# ir-24v.net
KiCad netlist of a schematic drawn in Altium Designer
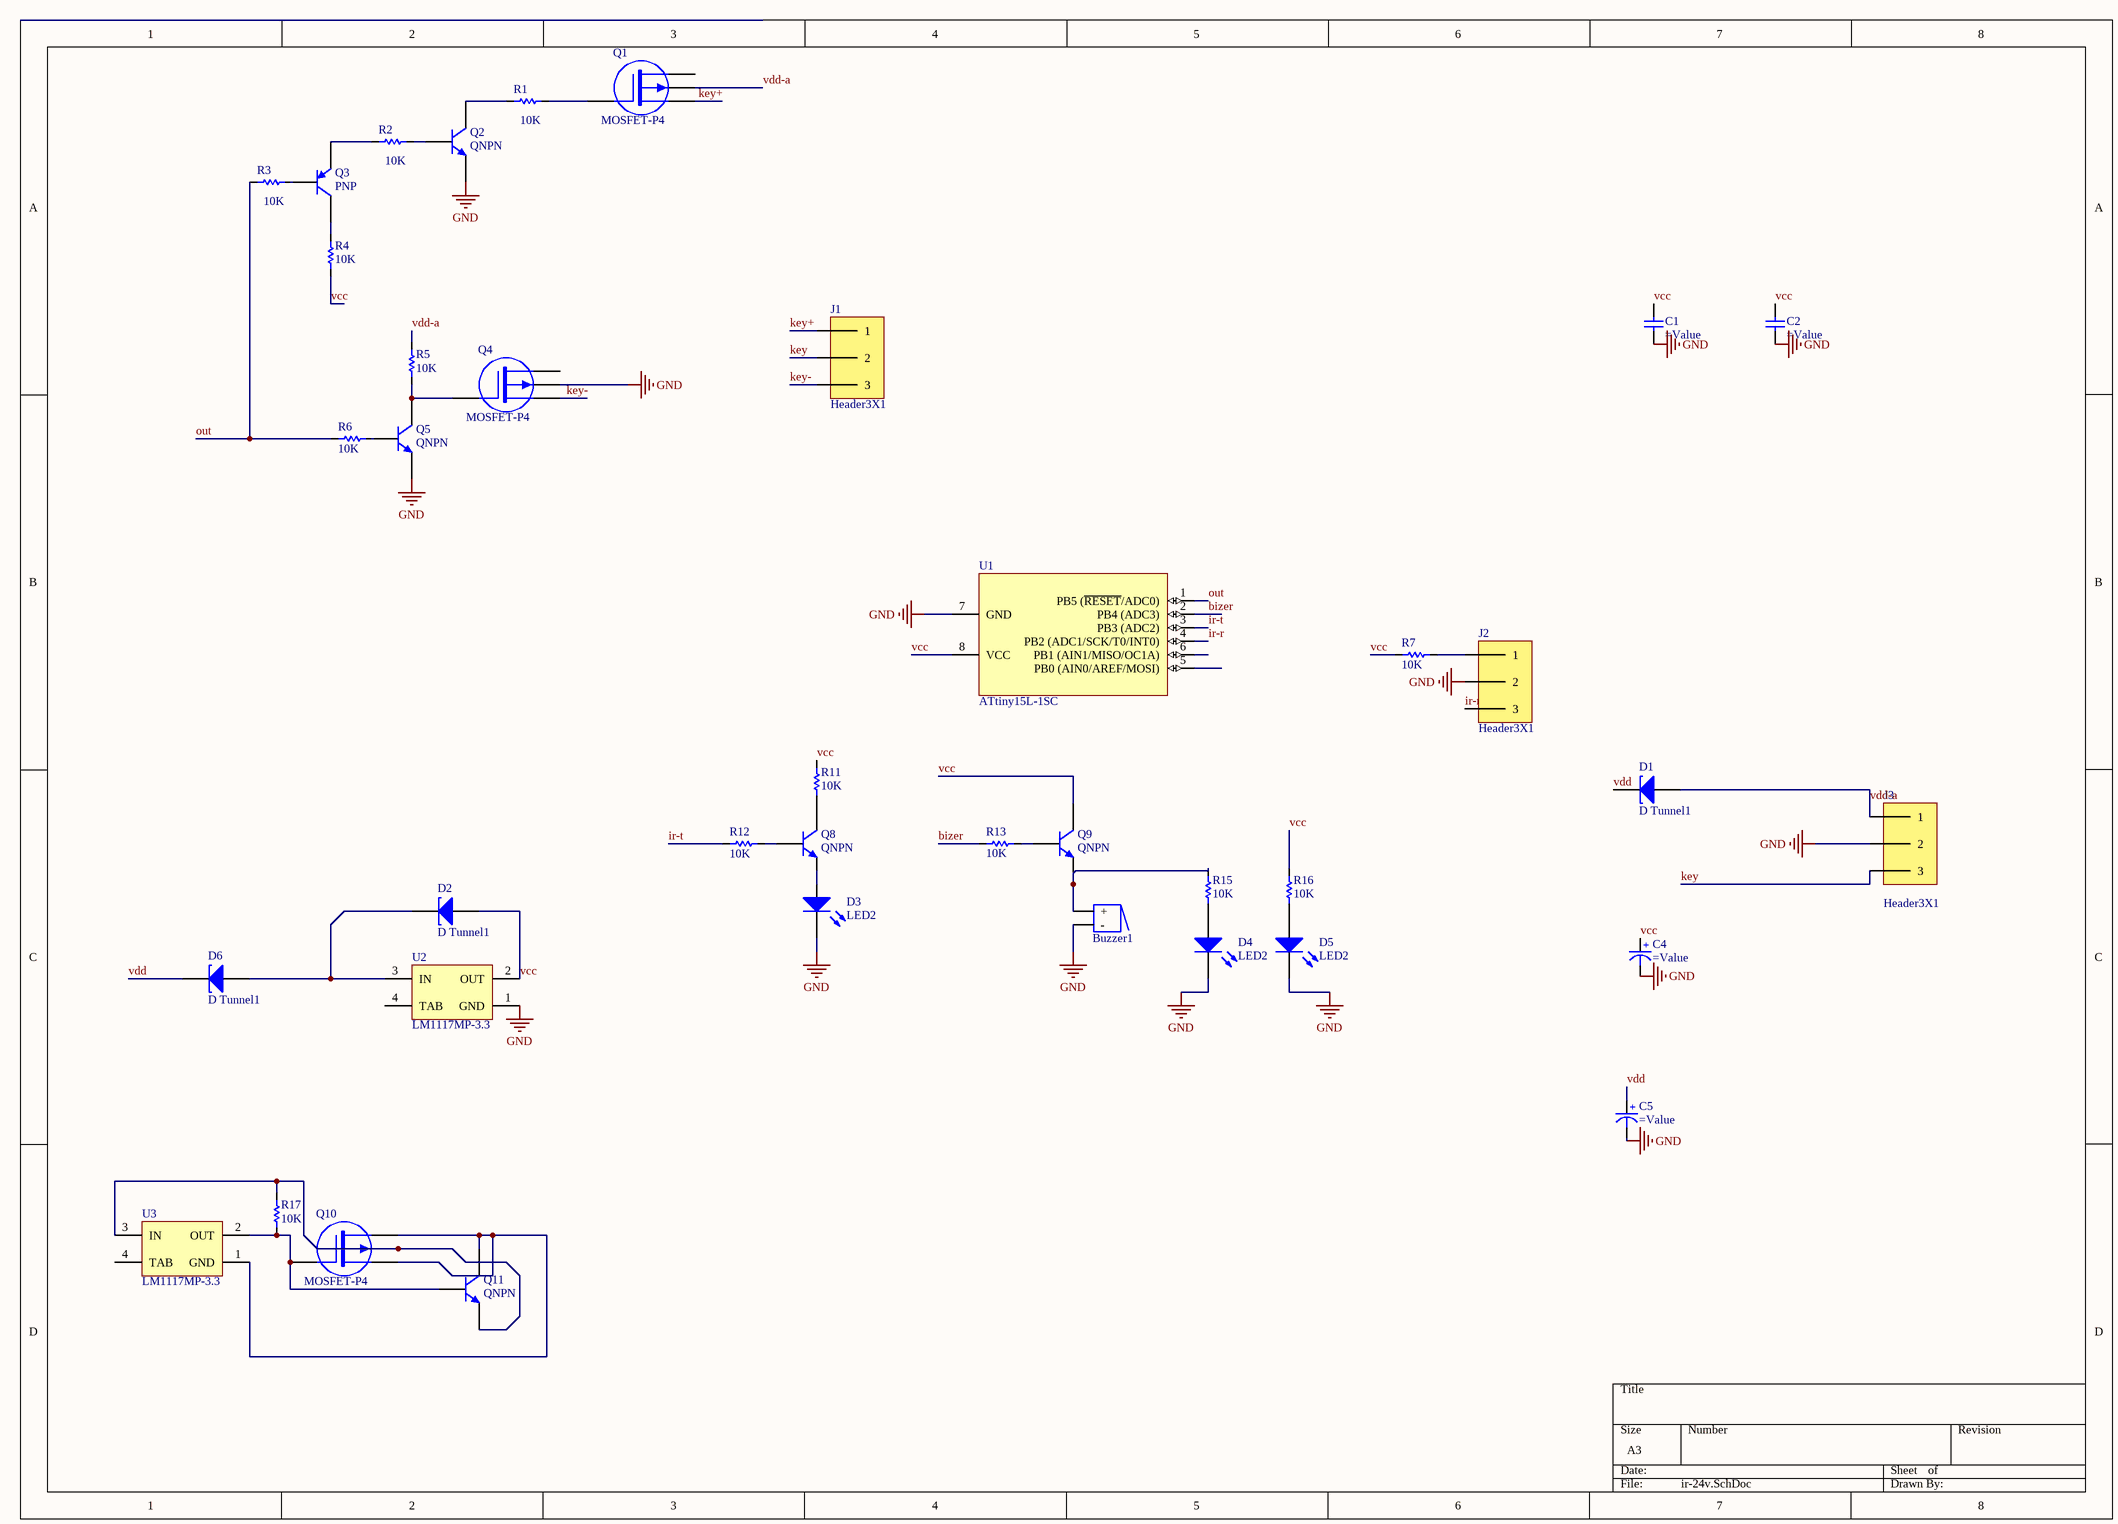
[diagram p0: ir-24v.SchDoc]

(export (version "E")
  (design (tool "Eeschema 10.0.6"))
  (components
    (comp (ref "Buzzer1")
      (value "Buzzer")
      (footprint "BUZZER")
      (fields (field (name "DESIGNER") "Seyed Mohsen Ghasemain"))
      (libsource (lib "PicPars.com_usefully_Library") (part "Buzzer"))
    )
    (comp (ref "C1")
      (value "~")
      (footprint "CAP 1206")
      (description "Capacitor")
      (libsource (lib "AltiumLib1") (part "Capacitor"))
    )
    (comp (ref "C2")
      (value "~")
      (footprint "CAP 1206")
      (description "Capacitor")
      (libsource (lib "AltiumLib1") (part "Capacitor"))
    )
    (comp (ref "C4")
      (value "~")
      (footprint "ELEC-CAP-RAD10-20")
      (description "Electrolytic Capacitor")
      (libsource (lib "AltiumLib1") (part "Capacitor Electrolytic"))
    )
    (comp (ref "C5")
      (value "~")
      (footprint "ELEC-CAP-RAD15-30")
      (description "Electrolytic Capacitor")
      (libsource (lib "AltiumLib1") (part "Capacitor Electrolytic"))
    )
    (comp (ref "D1")
      (value "D Tunnel1")
      (footprint "3.2X1.6X1.1")
      (description "Tunnel Diode - RLC Model")
      (fields (field (name "PUBLISHER") "Altium Limited"))
      (libsource (lib "Miscellaneous Devices") (part "D Tunnel1"))
    )
    (comp (ref "D2")
      (value "D Tunnel1")
      (footprint "3.2X1.6X1.1")
      (description "Tunnel Diode - RLC Model")
      (fields (field (name "PUBLISHER") "Altium Limited"))
      (libsource (lib "Miscellaneous Devices") (part "D Tunnel1"))
    )
    (comp (ref "D3")
      (value "LED2")
      (footprint "3.2X1.6X1.1")
      (description "Typical RED, GREEN, YELLOW, AMBER GaAs LED")
      (fields (field (name "PUBLISHER") "Altium Limited"))
      (libsource (lib "Miscellaneous Devices") (part "LED2"))
    )
    (comp (ref "D4")
      (value "LED2")
      (footprint "3.2X1.6X1.1")
      (description "Typical RED, GREEN, YELLOW, AMBER GaAs LED")
      (fields (field (name "PUBLISHER") "Altium Limited"))
      (libsource (lib "Miscellaneous Devices") (part "LED2"))
    )
    (comp (ref "D5")
      (value "LED2")
      (footprint "3.2X1.6X1.1")
      (description "Typical RED, GREEN, YELLOW, AMBER GaAs LED")
      (fields (field (name "PUBLISHER") "Altium Limited"))
      (libsource (lib "Miscellaneous Devices") (part "LED2"))
    )
    (comp (ref "D6")
      (value "D Tunnel1")
      (footprint "3.2X1.6X1.1")
      (description "Tunnel Diode - RLC Model")
      (fields (field (name "PUBLISHER") "Altium Limited"))
      (libsource (lib "Miscellaneous Devices") (part "D Tunnel1"))
    )
    (comp (ref "J1")
      (value "Header3X1")
      (footprint "HEADER 3X1")
      (libsource (lib "AltiumLib1") (part "Header3X1"))
    )
    (comp (ref "J2")
      (value "Header3X1")
      (footprint "HEADER 3X1")
      (libsource (lib "AltiumLib1") (part "Header3X1"))
    )
    (comp (ref "J3")
      (value "Header3X1")
      (footprint "HEADER 3X1")
      (libsource (lib "AltiumLib1") (part "Header3X1"))
    )
    (comp (ref "Q1")
      (value "MOSFET-P4")
      (footprint "SOT223_N")
      (description "P-Channel MOSFET, Externally Terminated Substrate")
      (fields (field (name "PUBLISHER") "Altium Limited"))
      (libsource (lib "Miscellaneous Devices") (part "MOSFET-P4"))
    )
    (comp (ref "Q2")
      (value "QNPN")
      (footprint "SOT-23B_L")
      (description "NPN Bipolar Transistor")
      (fields (field (name "PUBLISHER") "Altium Limited"))
      (libsource (lib "Miscellaneous Devices") (part "QNPN"))
    )
    (comp (ref "Q3")
      (value "PNP")
      (footprint "SOT-23B_N")
      (description "PNP Bipolar Transistor")
      (fields (field (name "PUBLISHER") "Altium Limited"))
      (libsource (lib "Miscellaneous Devices") (part "PNP"))
    )
    (comp (ref "Q4")
      (value "MOSFET-P4")
      (footprint "SOT223_N")
      (description "P-Channel MOSFET, Externally Terminated Substrate")
      (fields (field (name "PUBLISHER") "Altium Limited"))
      (libsource (lib "Miscellaneous Devices") (part "MOSFET-P4"))
    )
    (comp (ref "Q5")
      (value "QNPN")
      (footprint "SOT-23B_L")
      (description "NPN Bipolar Transistor")
      (fields (field (name "PUBLISHER") "Altium Limited"))
      (libsource (lib "Miscellaneous Devices") (part "QNPN"))
    )
    (comp (ref "Q8")
      (value "QNPN")
      (footprint "SOT-23B_L")
      (description "NPN Bipolar Transistor")
      (fields (field (name "PUBLISHER") "Altium Limited"))
      (libsource (lib "Miscellaneous Devices") (part "QNPN"))
    )
    (comp (ref "Q9")
      (value "QNPN")
      (footprint "SOT-23B_L")
      (description "NPN Bipolar Transistor")
      (fields (field (name "PUBLISHER") "Altium Limited"))
      (libsource (lib "Miscellaneous Devices") (part "QNPN"))
    )
    (comp (ref "Q10")
      (value "MOSFET-P4")
      (footprint "SOT223_N")
      (description "P-Channel MOSFET, Externally Terminated Substrate")
      (fields (field (name "PUBLISHER") "Altium Limited"))
      (libsource (lib "Miscellaneous Devices") (part "MOSFET-P4"))
    )
    (comp (ref "Q11")
      (value "QNPN")
      (footprint "SOT-23B_L")
      (description "NPN Bipolar Transistor")
      (fields (field (name "PUBLISHER") "Altium Limited"))
      (libsource (lib "Miscellaneous Devices") (part "QNPN"))
    )
    (comp (ref "R1")
      (value "10K")
      (footprint "RES 1206 (3216X08L)")
      (description "Resistor")
      (fields (field (name "TOLERANCE") "5%") (field (name "POWER") "1/4 W"))
      (libsource (lib "AltiumLib1") (part "Resistor"))
    )
    (comp (ref "R2")
      (value "10K")
      (footprint "RES 1206 (3216X08L)")
      (description "Resistor")
      (fields (field (name "TOLERANCE") "5%") (field (name "POWER") "1/4 W"))
      (libsource (lib "AltiumLib1") (part "Resistor"))
    )
    (comp (ref "R3")
      (value "10K")
      (footprint "RES 1206 (3216X08L)")
      (description "Resistor")
      (fields (field (name "TOLERANCE") "5%") (field (name "POWER") "1/4 W"))
      (libsource (lib "AltiumLib1") (part "Resistor"))
    )
    (comp (ref "R4")
      (value "10K")
      (footprint "RES 1206 (3216X08L)")
      (description "Resistor")
      (fields (field (name "TOLERANCE") "5%") (field (name "POWER") "1/4 W"))
      (libsource (lib "AltiumLib1") (part "Resistor"))
    )
    (comp (ref "R5")
      (value "10K")
      (footprint "RES 1206 (3216X08L)")
      (description "Resistor")
      (fields (field (name "TOLERANCE") "5%") (field (name "POWER") "1/4 W"))
      (libsource (lib "AltiumLib1") (part "Resistor"))
    )
    (comp (ref "R6")
      (value "10K")
      (footprint "RES 1206 (3216X08L)")
      (description "Resistor")
      (fields (field (name "TOLERANCE") "5%") (field (name "POWER") "1/4 W"))
      (libsource (lib "AltiumLib1") (part "Resistor"))
    )
    (comp (ref "R7")
      (value "10K")
      (footprint "RES 1206 (3216X08L)")
      (description "Resistor")
      (fields (field (name "TOLERANCE") "5%") (field (name "POWER") "1/4 W"))
      (libsource (lib "AltiumLib1") (part "Resistor"))
    )
    (comp (ref "R11")
      (value "10K")
      (footprint "RES 1206 (3216X08L)")
      (description "Resistor")
      (fields (field (name "TOLERANCE") "5%") (field (name "POWER") "1/4 W"))
      (libsource (lib "AltiumLib1") (part "Resistor"))
    )
    (comp (ref "R12")
      (value "10K")
      (footprint "RES 1206 (3216X08L)")
      (description "Resistor")
      (fields (field (name "TOLERANCE") "5%") (field (name "POWER") "1/4 W"))
      (libsource (lib "AltiumLib1") (part "Resistor"))
    )
    (comp (ref "R13")
      (value "10K")
      (footprint "RES 1206 (3216X08L)")
      (description "Resistor")
      (fields (field (name "TOLERANCE") "5%") (field (name "POWER") "1/4 W"))
      (libsource (lib "AltiumLib1") (part "Resistor"))
    )
    (comp (ref "R15")
      (value "10K")
      (footprint "RES 1206 (3216X08L)")
      (description "Resistor")
      (fields (field (name "TOLERANCE") "5%") (field (name "POWER") "1/4 W"))
      (libsource (lib "AltiumLib1") (part "Resistor"))
    )
    (comp (ref "R16")
      (value "10K")
      (footprint "RES 1206 (3216X08L)")
      (description "Resistor")
      (fields (field (name "TOLERANCE") "5%") (field (name "POWER") "1/4 W"))
      (libsource (lib "AltiumLib1") (part "Resistor"))
    )
    (comp (ref "R17")
      (value "10K")
      (footprint "RES 1206 (3216X08L)")
      (description "Resistor")
      (fields (field (name "TOLERANCE") "5%") (field (name "POWER") "1/4 W"))
      (libsource (lib "AltiumLib1") (part "Resistor"))
    )
    (comp (ref "U1")
      (value "ATtiny15L-1SC")
      (footprint "8S2_N")
      (description "8-Bit AVR Microcontroller with 1K Byte of Flash Memory")
      (fields (field (name "PUBLISHER") "Altium Limited"))
      (libsource (lib "Atmel Microcontroller 8-Bit AVR") (part "ATtiny15L-1SC"))
    )
    (comp (ref "U2")
      (value "LM1117MP-3.3")
      (footprint "Miscellaneous Devices:SOT89L")
      (description "800mA Low-Dropout Linear Regulator")
      (fields
        (field (name "MANUFACTURER") "National Semiconductor")
        (field (name "DIGIKEYPARTNUMBER") "LM1117MP-3.3CT-ND")
        (field (name "PUBLISHER") "Altium Limited")
      )
      (libsource (lib "NSC LDO") (part "LM1117MP-3.3"))
    )
    (comp (ref "U3")
      (value "LM1117MP-3.3")
      (footprint "Miscellaneous Devices:SOT89L")
      (description "800mA Low-Dropout Linear Regulator")
      (fields
        (field (name "MANUFACTURER") "National Semiconductor")
        (field (name "DIGIKEYPARTNUMBER") "LM1117MP-3.3CT-ND")
        (field (name "PUBLISHER") "Altium Limited")
      )
      (libsource (lib "NSC LDO") (part "LM1117MP-3.3"))
    )
  )
  (nets
    (net (code "1") (name "/bizer") (class "Default")
      (node (ref "R13") (pin "1") (pinfunction "1_1") (pintype "passive"))
      (node (ref "U1") (pin "2") (pinfunction "PB4_(ADC3)_2") (pintype "bidirectional"))
    )
    (net (code "2") (name "/ir-r") (class "Default")
      (node (ref "J2") (pin "3") (pinfunction "3_3") (pintype "passive"))
      (node (ref "U1") (pin "4") (pinfunction "PB2_(ADC1/SCK/T0/INT0)_4") (pintype "bidirectional"))
    )
    (net (code "3") (name "/ir-t") (class "Default")
      (node (ref "R12") (pin "1") (pinfunction "1_1") (pintype "passive"))
      (node (ref "U1") (pin "3") (pinfunction "PB3_(ADC2)_3") (pintype "bidirectional"))
    )
    (net (code "4") (name "/key") (class "Default")
      (node (ref "J1") (pin "2") (pinfunction "2_2") (pintype "passive"))
      (node (ref "J3") (pin "3") (pinfunction "3_3") (pintype "passive"))
    )
    (net (code "5") (name "/key+") (class "Default")
      (node (ref "J1") (pin "1") (pinfunction "1_1") (pintype "passive"))
      (node (ref "Q1") (pin "4") (pinfunction "S_4") (pintype "passive"))
    )
    (net (code "6") (name "/key-") (class "Default")
      (node (ref "J1") (pin "3") (pinfunction "3_3") (pintype "passive"))
      (node (ref "Q4") (pin "4") (pinfunction "S_4") (pintype "passive"))
    )
    (net (code "7") (name "/out") (class "Default")
      (node (ref "R3") (pin "1") (pinfunction "1_1") (pintype "passive"))
      (node (ref "R6") (pin "1") (pinfunction "1_1") (pintype "passive"))
      (node (ref "U1") (pin "1") (pinfunction "PB5_(~{RESET}/ADC0)_1") (pintype "bidirectional"))
    )
    (net (code "8") (name "/vcc") (class "Default")
      (node (ref "C1") (pin "2") (pinfunction "-_2") (pintype "passive"))
      (node (ref "C2") (pin "2") (pinfunction "-_2") (pintype "passive"))
      (node (ref "C4") (pin "2") (pinfunction "+_2") (pintype "passive"))
      (node (ref "D2") (pin "1") (pinfunction "A_1") (pintype "passive"))
      (node (ref "Q9") (pin "1") (pinfunction "C_1") (pintype "passive"))
      (node (ref "R11") (pin "2") (pinfunction "2_2") (pintype "passive"))
      (node (ref "R16") (pin "2") (pinfunction "2_2") (pintype "passive"))
      (node (ref "R4") (pin "2") (pinfunction "2_2") (pintype "passive"))
      (node (ref "R7") (pin "2") (pinfunction "2_2") (pintype "passive"))
      (node (ref "U1") (pin "8") (pinfunction "VCC_8") (pintype "power_in"))
      (node (ref "U2") (pin "2") (pinfunction "OUT_2") (pintype "power_in"))
    )
    (net (code "9") (name "/vdd") (class "Default")
      (node (ref "C5") (pin "2") (pinfunction "+_2") (pintype "passive"))
      (node (ref "D1") (pin "2") (pinfunction "K_2") (pintype "passive"))
      (node (ref "D6") (pin "2") (pinfunction "K_2") (pintype "passive"))
    )
    (net (code "10") (name "/vdd-a") (class "Default")
      (node (ref "D1") (pin "1") (pinfunction "A_1") (pintype "passive"))
      (node (ref "J3") (pin "1") (pinfunction "1_1") (pintype "passive"))
      (node (ref "Q1") (pin "3") (pinfunction "U_3") (pintype "passive"))
      (node (ref "R5") (pin "2") (pinfunction "2_2") (pintype "passive"))
    )
    (net (code "11") (name "GND") (class "Default")
      (node (ref "Buzzer1") (pin "2") (pinfunction "-_2") (pintype "passive"))
      (node (ref "C1") (pin "1") (pinfunction "+_1") (pintype "passive"))
      (node (ref "C2") (pin "1") (pinfunction "+_1") (pintype "passive"))
      (node (ref "C4") (pin "1") (pinfunction "-_1") (pintype "passive"))
      (node (ref "C5") (pin "1") (pinfunction "-_1") (pintype "passive"))
      (node (ref "D3") (pin "2") (pinfunction "K_2") (pintype "passive"))
      (node (ref "D4") (pin "2") (pinfunction "K_2") (pintype "passive"))
      (node (ref "D5") (pin "2") (pinfunction "K_2") (pintype "passive"))
      (node (ref "J2") (pin "2") (pinfunction "2_2") (pintype "passive"))
      (node (ref "J3") (pin "2") (pinfunction "2_2") (pintype "passive"))
      (node (ref "Q2") (pin "3") (pinfunction "E_3") (pintype "passive"))
      (node (ref "Q4") (pin "3") (pinfunction "U_3") (pintype "passive"))
      (node (ref "Q5") (pin "3") (pinfunction "E_3") (pintype "passive"))
      (node (ref "U1") (pin "7") (pinfunction "GND_7") (pintype "power_in"))
      (node (ref "U2") (pin "1") (pinfunction "GND_1") (pintype "power_in"))
    )
    (net (code "12") (name "Net-(Buzzer1-+)") (class "Default")
      (node (ref "Buzzer1") (pin "1") (pinfunction "+_1") (pintype "passive"))
      (node (ref "Q9") (pin "3") (pinfunction "E_3") (pintype "passive"))
      (node (ref "R15") (pin "2") (pinfunction "2_2") (pintype "passive"))
    )
    (net (code "13") (name "Net-(D2-K)") (class "Default")
      (node (ref "D2") (pin "2") (pinfunction "K_2") (pintype "passive"))
      (node (ref "D6") (pin "1") (pinfunction "A_1") (pintype "passive"))
      (node (ref "U2") (pin "3") (pinfunction "IN_3") (pintype "power_in"))
    )
    (net (code "14") (name "Net-(D3-A)") (class "Default")
      (node (ref "D3") (pin "1") (pinfunction "A_1") (pintype "passive"))
      (node (ref "Q8") (pin "3") (pinfunction "E_3") (pintype "passive"))
    )
    (net (code "15") (name "Net-(D4-A)") (class "Default")
      (node (ref "D4") (pin "1") (pinfunction "A_1") (pintype "passive"))
      (node (ref "R15") (pin "1") (pinfunction "1_1") (pintype "passive"))
    )
    (net (code "16") (name "Net-(D5-A)") (class "Default")
      (node (ref "D5") (pin "1") (pinfunction "A_1") (pintype "passive"))
      (node (ref "R16") (pin "1") (pinfunction "1_1") (pintype "passive"))
    )
    (net (code "17") (name "Net-(J2-Pad1)") (class "Default")
      (node (ref "J2") (pin "1") (pinfunction "1_1") (pintype "passive"))
      (node (ref "R7") (pin "1") (pinfunction "1_1") (pintype "passive"))
    )
    (net (code "18") (name "Net-(Q1-G)") (class "Default")
      (node (ref "Q1") (pin "1") (pinfunction "G_1") (pintype "passive"))
      (node (ref "R1") (pin "2") (pinfunction "2_2") (pintype "passive"))
    )
    (net (code "19") (name "Net-(Q2-B)") (class "Default")
      (node (ref "Q2") (pin "2") (pinfunction "B_2") (pintype "passive"))
      (node (ref "R2") (pin "2") (pinfunction "2_2") (pintype "passive"))
    )
    (net (code "20") (name "Net-(Q2-C)") (class "Default")
      (node (ref "Q2") (pin "1") (pinfunction "C_1") (pintype "passive"))
      (node (ref "R1") (pin "1") (pinfunction "1_1") (pintype "passive"))
    )
    (net (code "21") (name "Net-(Q3-B)") (class "Default")
      (node (ref "Q3") (pin "2") (pinfunction "B_2") (pintype "passive"))
      (node (ref "R3") (pin "2") (pinfunction "2_2") (pintype "passive"))
    )
    (net (code "22") (name "Net-(Q3-C)") (class "Default")
      (node (ref "Q3") (pin "1") (pinfunction "C_1") (pintype "passive"))
      (node (ref "R4") (pin "1") (pinfunction "1_1") (pintype "passive"))
    )
    (net (code "23") (name "Net-(Q3-E)") (class "Default")
      (node (ref "Q3") (pin "3") (pinfunction "E_3") (pintype "passive"))
      (node (ref "R2") (pin "1") (pinfunction "1_1") (pintype "passive"))
    )
    (net (code "24") (name "Net-(Q4-G)") (class "Default")
      (node (ref "Q4") (pin "1") (pinfunction "G_1") (pintype "passive"))
      (node (ref "Q5") (pin "1") (pinfunction "C_1") (pintype "passive"))
      (node (ref "R5") (pin "1") (pinfunction "1_1") (pintype "passive"))
    )
    (net (code "25") (name "Net-(Q5-B)") (class "Default")
      (node (ref "Q5") (pin "2") (pinfunction "B_2") (pintype "passive"))
      (node (ref "R6") (pin "2") (pinfunction "2_2") (pintype "passive"))
    )
    (net (code "26") (name "Net-(Q8-B)") (class "Default")
      (node (ref "Q8") (pin "2") (pinfunction "B_2") (pintype "passive"))
      (node (ref "R12") (pin "2") (pinfunction "2_2") (pintype "passive"))
    )
    (net (code "27") (name "Net-(Q8-C)") (class "Default")
      (node (ref "Q8") (pin "1") (pinfunction "C_1") (pintype "passive"))
      (node (ref "R11") (pin "1") (pinfunction "1_1") (pintype "passive"))
    )
    (net (code "28") (name "Net-(Q9-B)") (class "Default")
      (node (ref "Q9") (pin "2") (pinfunction "B_2") (pintype "passive"))
      (node (ref "R13") (pin "2") (pinfunction "2_2") (pintype "passive"))
    )
    (net (code "29") (name "Net-(Q10-D)") (class "Default")
      (node (ref "Q10") (pin "2") (pinfunction "D_2") (pintype "passive"))
      (node (ref "Q10") (pin "4") (pinfunction "S_4") (pintype "passive"))
      (node (ref "Q11") (pin "1") (pinfunction "C_1") (pintype "passive"))
      (node (ref "U3") (pin "1") (pinfunction "GND_1") (pintype "power_in"))
    )
    (net (code "30") (name "Net-(Q10-G)") (class "Default")
      (node (ref "Q10") (pin "1") (pinfunction "G_1") (pintype "passive"))
      (node (ref "Q11") (pin "2") (pinfunction "B_2") (pintype "passive"))
      (node (ref "R17") (pin "1") (pinfunction "1_1") (pintype "passive"))
      (node (ref "U3") (pin "2") (pinfunction "OUT_2") (pintype "power_in"))
    )
    (net (code "31") (name "Net-(Q10-U)") (class "Default")
      (node (ref "Q10") (pin "3") (pinfunction "U_3") (pintype "passive"))
      (node (ref "Q11") (pin "3") (pinfunction "E_3") (pintype "passive"))
      (node (ref "R17") (pin "2") (pinfunction "2_2") (pintype "passive"))
      (node (ref "U3") (pin "3") (pinfunction "IN_3") (pintype "power_in"))
    )
    (net (code "32") (name "unconnected-(Q1-D-Pad2)") (class "Default")
      (node (ref "Q1") (pin "2") (pinfunction "D_2") (pintype "passive"))
    )
    (net (code "33") (name "unconnected-(Q4-D-Pad2)") (class "Default")
      (node (ref "Q4") (pin "2") (pinfunction "D_2") (pintype "passive"))
    )
    (net (code "34") (name "unconnected-(U1-PB0_(AIN0{slash}AREF{slash}MOSI)-Pad5)") (class "Default")
      (node (ref "U1") (pin "5") (pinfunction "PB0_(AIN0/AREF/MOSI)_5") (pintype "bidirectional"))
    )
    (net (code "35") (name "unconnected-(U1-PB1_(AIN1{slash}MISO{slash}OC1A)-Pad6)") (class "Default")
      (node (ref "U1") (pin "6") (pinfunction "PB1_(AIN1/MISO/OC1A)_6") (pintype "bidirectional"))
    )
    (net (code "36") (name "unconnected-(U2-TAB-Pad4)") (class "Default")
      (node (ref "U2") (pin "4") (pinfunction "TAB_4") (pintype "power_in"))
    )
    (net (code "37") (name "unconnected-(U3-TAB-Pad4)") (class "Default")
      (node (ref "U3") (pin "4") (pinfunction "TAB_4") (pintype "power_in"))
    )
  )
)
